# Memory.net
KiCad netlist of a schematic drawn in EAGLE
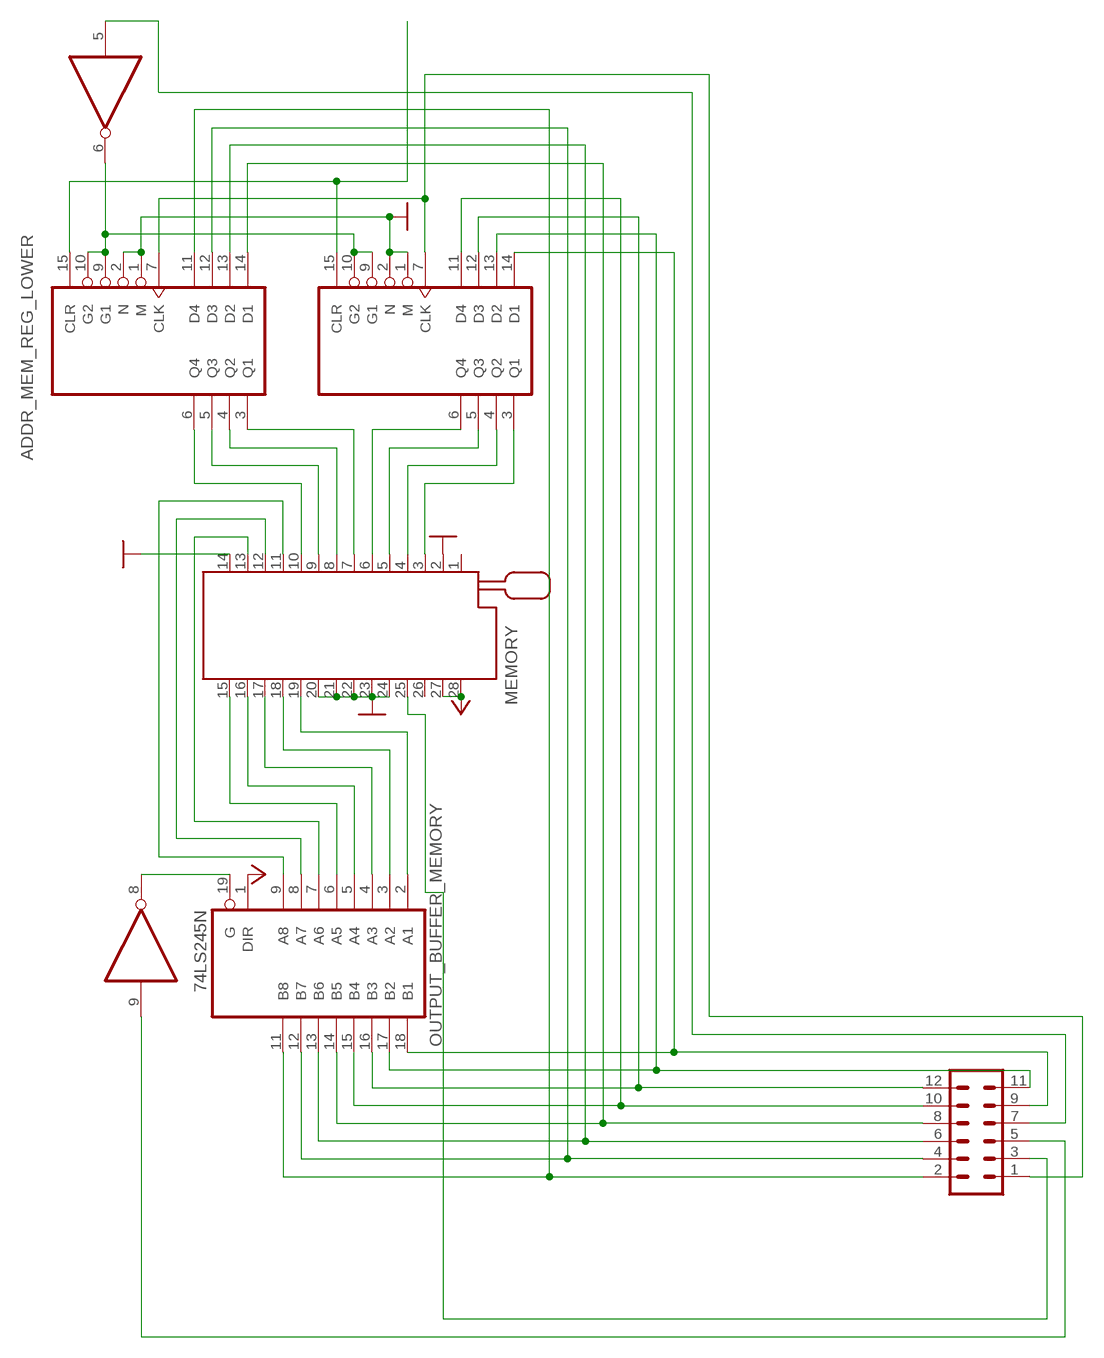
[diagram p0: schematic, sheet 1]

(export (version "E")
  (design (tool "Eeschema 10.0.6"))
  (components
    (comp (ref "ADDR_MEM_REG_LOWER")
      (value "74LS173N")
      (footprint "eagle-import:DIL16")
      (libsource (lib "eagle-import") (part "74173NLS"))
    )
    (comp (ref "ADDR_MEM_REG_UPPER")
      (value "74LS173N")
      (footprint "eagle-import:DIL16")
      (libsource (lib "eagle-import") (part "74173NLS"))
    )
    (comp (ref "MEMORY")
      (value "228-1277-00-0602J")
      (footprint "eagle-import:228-1277-00-0602J")
      (fields (field (name "MF") "3M"))
      (libsource (lib "eagle-import") (part "228-?00-0602J1277-"))
    )
    (comp (ref "NOT_GATE1_")
      (value "74LS04N")
      (footprint "eagle-import:DIL14")
      (libsource (lib "eagle-import") (part "7404NLS"))
    )
    (comp (ref "OUTPUT_BUFFER_MEMORY")
      (value "74LS245N")
      (footprint "eagle-import:DIL20")
      (libsource (lib "eagle-import") (part "74245NLS"))
    )
    (comp (ref "SV1")
      (value "MA06-2")
      (footprint "eagle-import:MA06-2")
      (libsource (lib "eagle-import") (part "MA06-2"))
    )
  )
  (nets
    (net (code "1") (name "GND") (class "Default")
      (node (ref "ADDR_MEM_REG_LOWER") (pin "1") (pinfunction "M_1") (pintype "input"))
      (node (ref "ADDR_MEM_REG_LOWER") (pin "2") (pinfunction "N_2") (pintype "input"))
      (node (ref "ADDR_MEM_REG_UPPER") (pin "1") (pinfunction "M_1") (pintype "input"))
      (node (ref "ADDR_MEM_REG_UPPER") (pin "2") (pinfunction "N_2") (pintype "input"))
      (node (ref "MEMORY") (pin "14") (pinfunction "14_14") (pintype "passive"))
      (node (ref "MEMORY") (pin "2") (pinfunction "2_2") (pintype "passive"))
      (node (ref "MEMORY") (pin "20") (pinfunction "20_20") (pintype "passive"))
      (node (ref "MEMORY") (pin "21") (pinfunction "21_21") (pintype "passive"))
      (node (ref "MEMORY") (pin "22") (pinfunction "22_22") (pintype "passive"))
      (node (ref "MEMORY") (pin "23") (pinfunction "23_23") (pintype "passive"))
      (node (ref "MEMORY") (pin "24") (pinfunction "24_24") (pintype "passive"))
    )
    (net (code "2") (name "Net-(ADDR_MEM_REG_LOWERA-CLK)") (class "Default")
      (node (ref "ADDR_MEM_REG_LOWER") (pin "7") (pinfunction "CLK_7") (pintype "input"))
      (node (ref "ADDR_MEM_REG_UPPER") (pin "7") (pinfunction "CLK_7") (pintype "input"))
      (node (ref "SV1") (pin "1") (pinfunction "1_1") (pintype "passive"))
    )
    (net (code "3") (name "Net-(ADDR_MEM_REG_LOWERA-CLR)") (class "Default")
      (node (ref "ADDR_MEM_REG_LOWER") (pin "15") (pinfunction "CLR_15") (pintype "input"))
      (node (ref "ADDR_MEM_REG_UPPER") (pin "15") (pinfunction "CLR_15") (pintype "input"))
    )
    (net (code "4") (name "Net-(ADDR_MEM_REG_LOWERA-D1)") (class "Default")
      (node (ref "ADDR_MEM_REG_LOWER") (pin "14") (pinfunction "D1_14") (pintype "input"))
      (node (ref "OUTPUT_BUFFER_MEMORY") (pin "14") (pinfunction "B5_14") (pintype "bidirectional"))
      (node (ref "SV1") (pin "8") (pinfunction "8_8") (pintype "passive"))
    )
    (net (code "5") (name "Net-(ADDR_MEM_REG_LOWERA-D2)") (class "Default")
      (node (ref "ADDR_MEM_REG_LOWER") (pin "13") (pinfunction "D2_13") (pintype "input"))
      (node (ref "OUTPUT_BUFFER_MEMORY") (pin "13") (pinfunction "B6_13") (pintype "bidirectional"))
      (node (ref "SV1") (pin "6") (pinfunction "6_6") (pintype "passive"))
    )
    (net (code "6") (name "Net-(ADDR_MEM_REG_LOWERA-D3)") (class "Default")
      (node (ref "ADDR_MEM_REG_LOWER") (pin "12") (pinfunction "D3_12") (pintype "input"))
      (node (ref "OUTPUT_BUFFER_MEMORY") (pin "12") (pinfunction "B7_12") (pintype "bidirectional"))
      (node (ref "SV1") (pin "4") (pinfunction "4_4") (pintype "passive"))
    )
    (net (code "7") (name "Net-(ADDR_MEM_REG_LOWERA-D4)") (class "Default")
      (node (ref "ADDR_MEM_REG_LOWER") (pin "11") (pinfunction "D4_11") (pintype "input"))
      (node (ref "OUTPUT_BUFFER_MEMORY") (pin "11") (pinfunction "B8_11") (pintype "bidirectional"))
      (node (ref "SV1") (pin "2") (pinfunction "2_2") (pintype "passive"))
    )
    (net (code "8") (name "Net-(ADDR_MEM_REG_LOWERA-G1)") (class "Default")
      (node (ref "ADDR_MEM_REG_LOWER") (pin "10") (pinfunction "G2_10") (pintype "input"))
      (node (ref "ADDR_MEM_REG_LOWER") (pin "9") (pinfunction "G1_9") (pintype "input"))
      (node (ref "ADDR_MEM_REG_UPPER") (pin "10") (pinfunction "G2_10") (pintype "input"))
      (node (ref "ADDR_MEM_REG_UPPER") (pin "9") (pinfunction "G1_9") (pintype "input"))
      (node (ref "NOT_GATE1_") (pin "6") (pinfunction "O_6") (pintype "output"))
    )
    (net (code "9") (name "Net-(ADDR_MEM_REG_LOWERA-Q1)") (class "Default")
      (node (ref "ADDR_MEM_REG_LOWER") (pin "3") (pinfunction "Q1_3") (pintype "tri_state"))
      (node (ref "MEMORY") (pin "7") (pinfunction "7_7") (pintype "passive"))
    )
    (net (code "10") (name "Net-(ADDR_MEM_REG_LOWERA-Q2)") (class "Default")
      (node (ref "ADDR_MEM_REG_LOWER") (pin "4") (pinfunction "Q2_4") (pintype "tri_state"))
      (node (ref "MEMORY") (pin "8") (pinfunction "8_8") (pintype "passive"))
    )
    (net (code "11") (name "Net-(ADDR_MEM_REG_LOWERA-Q3)") (class "Default")
      (node (ref "ADDR_MEM_REG_LOWER") (pin "5") (pinfunction "Q3_5") (pintype "tri_state"))
      (node (ref "MEMORY") (pin "9") (pinfunction "9_9") (pintype "passive"))
    )
    (net (code "12") (name "Net-(ADDR_MEM_REG_LOWERA-Q4)") (class "Default")
      (node (ref "ADDR_MEM_REG_LOWER") (pin "6") (pinfunction "Q4_6") (pintype "tri_state"))
      (node (ref "MEMORY") (pin "10") (pinfunction "10_10") (pintype "passive"))
    )
    (net (code "13") (name "Net-(ADDR_MEM_REG_UPPERA-D1)") (class "Default")
      (node (ref "ADDR_MEM_REG_UPPER") (pin "14") (pinfunction "D1_14") (pintype "input"))
      (node (ref "OUTPUT_BUFFER_MEMORY") (pin "18") (pinfunction "B1_18") (pintype "bidirectional"))
      (node (ref "SV1") (pin "9") (pinfunction "9_9") (pintype "passive"))
    )
    (net (code "14") (name "Net-(ADDR_MEM_REG_UPPERA-D2)") (class "Default")
      (node (ref "ADDR_MEM_REG_UPPER") (pin "13") (pinfunction "D2_13") (pintype "input"))
      (node (ref "OUTPUT_BUFFER_MEMORY") (pin "17") (pinfunction "B2_17") (pintype "bidirectional"))
      (node (ref "SV1") (pin "11") (pinfunction "11_11") (pintype "passive"))
    )
    (net (code "15") (name "Net-(ADDR_MEM_REG_UPPERA-D3)") (class "Default")
      (node (ref "ADDR_MEM_REG_UPPER") (pin "12") (pinfunction "D3_12") (pintype "input"))
      (node (ref "OUTPUT_BUFFER_MEMORY") (pin "16") (pinfunction "B3_16") (pintype "bidirectional"))
      (node (ref "SV1") (pin "12") (pinfunction "12_12") (pintype "passive"))
    )
    (net (code "16") (name "Net-(ADDR_MEM_REG_UPPERA-D4)") (class "Default")
      (node (ref "ADDR_MEM_REG_UPPER") (pin "11") (pinfunction "D4_11") (pintype "input"))
      (node (ref "OUTPUT_BUFFER_MEMORY") (pin "15") (pinfunction "B4_15") (pintype "bidirectional"))
      (node (ref "SV1") (pin "10") (pinfunction "10_10") (pintype "passive"))
    )
    (net (code "17") (name "Net-(ADDR_MEM_REG_UPPERA-Q1)") (class "Default")
      (node (ref "ADDR_MEM_REG_UPPER") (pin "3") (pinfunction "Q1_3") (pintype "tri_state"))
      (node (ref "MEMORY") (pin "3") (pinfunction "3_3") (pintype "passive"))
    )
    (net (code "18") (name "Net-(ADDR_MEM_REG_UPPERA-Q2)") (class "Default")
      (node (ref "ADDR_MEM_REG_UPPER") (pin "4") (pinfunction "Q2_4") (pintype "tri_state"))
      (node (ref "MEMORY") (pin "4") (pinfunction "4_4") (pintype "passive"))
    )
    (net (code "19") (name "Net-(ADDR_MEM_REG_UPPERA-Q3)") (class "Default")
      (node (ref "ADDR_MEM_REG_UPPER") (pin "5") (pinfunction "Q3_5") (pintype "tri_state"))
      (node (ref "MEMORY") (pin "5") (pinfunction "5_5") (pintype "passive"))
    )
    (net (code "20") (name "Net-(ADDR_MEM_REG_UPPERA-Q4)") (class "Default")
      (node (ref "ADDR_MEM_REG_UPPER") (pin "6") (pinfunction "Q4_6") (pintype "tri_state"))
      (node (ref "MEMORY") (pin "6") (pinfunction "6_6") (pintype "passive"))
    )
    (net (code "21") (name "Net-(MEMORY-Pad25)") (class "Default")
      (node (ref "MEMORY") (pin "25") (pinfunction "25_25") (pintype "passive"))
      (node (ref "SV1") (pin "3") (pinfunction "3_3") (pintype "passive"))
    )
    (net (code "22") (name "Net-(NOT_GATE1_C-I)") (class "Default")
      (node (ref "NOT_GATE1_") (pin "5") (pinfunction "I_5") (pintype "input"))
      (node (ref "SV1") (pin "7") (pinfunction "7_7") (pintype "passive"))
    )
    (net (code "23") (name "Net-(NOT_GATE1_D-I)") (class "Default")
      (node (ref "NOT_GATE1_") (pin "9") (pinfunction "I_9") (pintype "input"))
      (node (ref "SV1") (pin "5") (pinfunction "5_5") (pintype "passive"))
    )
    (net (code "24") (name "Net-(NOT_GATE1_D-O)") (class "Default")
      (node (ref "NOT_GATE1_") (pin "8") (pinfunction "O_8") (pintype "output"))
      (node (ref "OUTPUT_BUFFER_MEMORY") (pin "19") (pinfunction "G_19") (pintype "input"))
    )
    (net (code "25") (name "Net-(OUTPUT_BUFFER_MEMORYA-A1)") (class "Default")
      (node (ref "MEMORY") (pin "19") (pinfunction "19_19") (pintype "passive"))
      (node (ref "OUTPUT_BUFFER_MEMORY") (pin "2") (pinfunction "A1_2") (pintype "bidirectional"))
    )
    (net (code "26") (name "Net-(OUTPUT_BUFFER_MEMORYA-A2)") (class "Default")
      (node (ref "MEMORY") (pin "18") (pinfunction "18_18") (pintype "passive"))
      (node (ref "OUTPUT_BUFFER_MEMORY") (pin "3") (pinfunction "A2_3") (pintype "bidirectional"))
    )
    (net (code "27") (name "Net-(OUTPUT_BUFFER_MEMORYA-A3)") (class "Default")
      (node (ref "MEMORY") (pin "17") (pinfunction "17_17") (pintype "passive"))
      (node (ref "OUTPUT_BUFFER_MEMORY") (pin "4") (pinfunction "A3_4") (pintype "bidirectional"))
    )
    (net (code "28") (name "Net-(OUTPUT_BUFFER_MEMORYA-A4)") (class "Default")
      (node (ref "MEMORY") (pin "16") (pinfunction "16_16") (pintype "passive"))
      (node (ref "OUTPUT_BUFFER_MEMORY") (pin "5") (pinfunction "A4_5") (pintype "bidirectional"))
    )
    (net (code "29") (name "Net-(OUTPUT_BUFFER_MEMORYA-A5)") (class "Default")
      (node (ref "MEMORY") (pin "15") (pinfunction "15_15") (pintype "passive"))
      (node (ref "OUTPUT_BUFFER_MEMORY") (pin "6") (pinfunction "A5_6") (pintype "bidirectional"))
    )
    (net (code "30") (name "Net-(OUTPUT_BUFFER_MEMORYA-A6)") (class "Default")
      (node (ref "MEMORY") (pin "13") (pinfunction "13_13") (pintype "passive"))
      (node (ref "OUTPUT_BUFFER_MEMORY") (pin "7") (pinfunction "A6_7") (pintype "bidirectional"))
    )
    (net (code "31") (name "Net-(OUTPUT_BUFFER_MEMORYA-A7)") (class "Default")
      (node (ref "MEMORY") (pin "12") (pinfunction "12_12") (pintype "passive"))
      (node (ref "OUTPUT_BUFFER_MEMORY") (pin "8") (pinfunction "A7_8") (pintype "bidirectional"))
    )
    (net (code "32") (name "Net-(OUTPUT_BUFFER_MEMORYA-A8)") (class "Default")
      (node (ref "MEMORY") (pin "11") (pinfunction "11_11") (pintype "passive"))
      (node (ref "OUTPUT_BUFFER_MEMORY") (pin "9") (pinfunction "A8_9") (pintype "bidirectional"))
    )
    (net (code "33") (name "VCC") (class "Default")
      (node (ref "MEMORY") (pin "27") (pinfunction "27_27") (pintype "passive"))
      (node (ref "MEMORY") (pin "28") (pinfunction "28_28") (pintype "passive"))
      (node (ref "OUTPUT_BUFFER_MEMORY") (pin "1") (pinfunction "DIR_1") (pintype "input"))
    )
    (net (code "34") (name "unconnected-(MEMORY-Pad1)") (class "Default")
      (node (ref "MEMORY") (pin "1") (pinfunction "1_1") (pintype "passive"))
    )
    (net (code "35") (name "unconnected-(MEMORY-Pad26)") (class "Default")
      (node (ref "MEMORY") (pin "26") (pinfunction "26_26") (pintype "passive"))
    )
  )
)
